# STM32F103_Debugger.net
KiCad netlist of a schematic drawn in Altium Designer
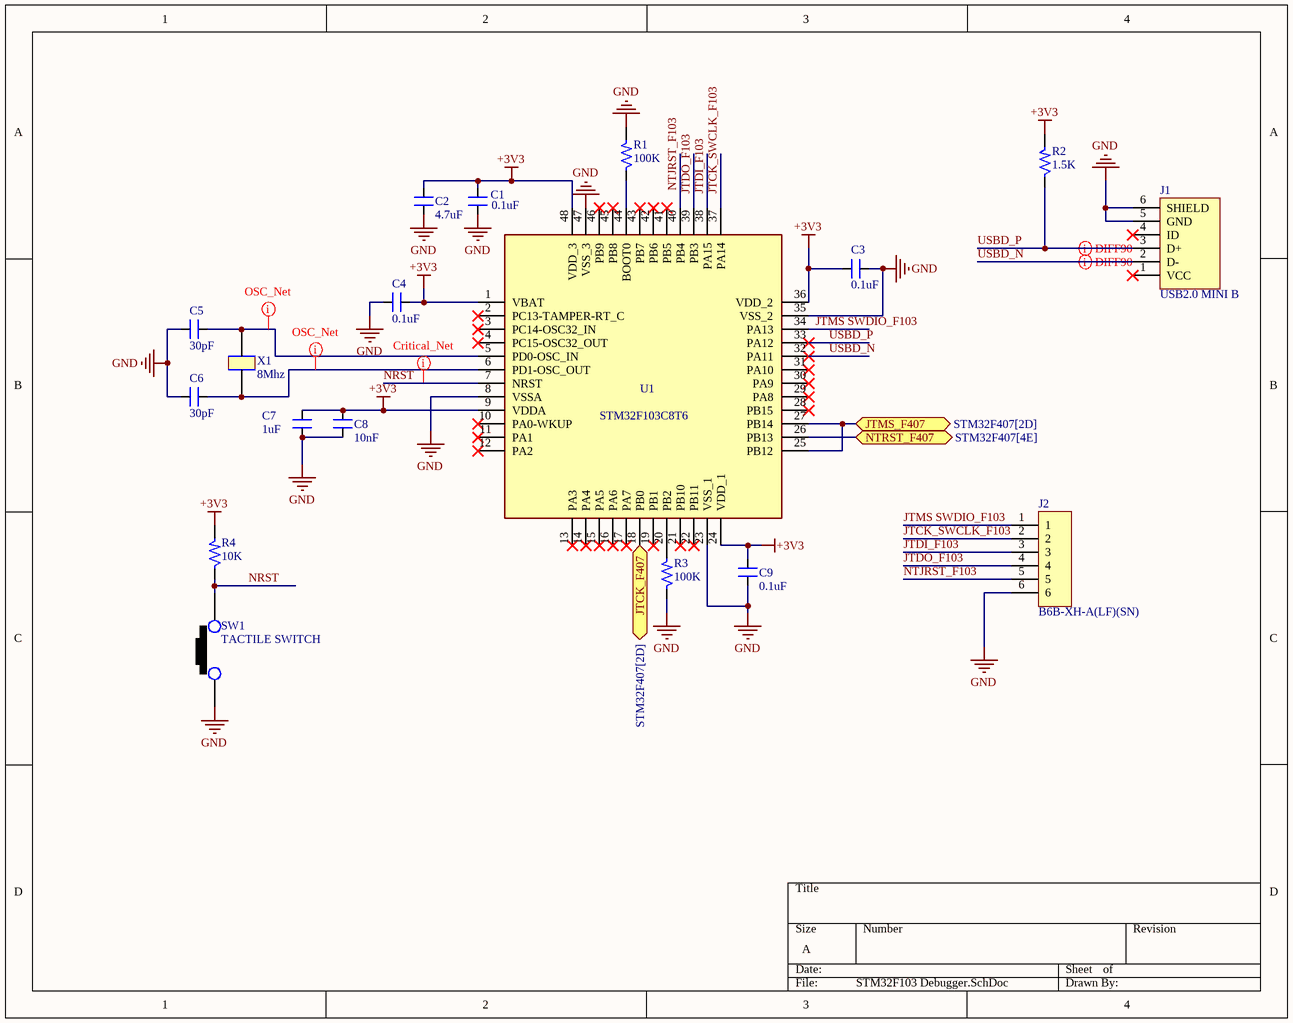
[diagram p0: STM32F103 Debugger.SchDoc]

(export (version "E")
  (design (tool "Eeschema 10.0.6"))
  (components
    (comp (ref "C1")
      (value "0.1uF")
      (footprint "CAP_0805")
      (description "0.1µF ±10% 50V Ceramic Capacitor X7R 0805 (2012 Metric)")
      (fields
        (field (name "MANUFACTURER") "Samsung")
        (field (name "MANUFACTURER PART NUMBER") "CL21B104KBCNNNC")
      )
      (libsource (lib "ESTEEMPCBLIB") (part "CAP_0.1uF-50V-10%-0805"))
    )
    (comp (ref "C2")
      (value "4.7uF")
      (footprint "CAP_0805")
      (description "4.7µF ±10% 50V Ceramic Capacitor X5R 0805 (2012 Metric)")
      (fields
        (field (name "MANUFACTURER") "Yageo")
        (field (name "MANUFACTURER PART NUMBER") "GRM21BR61H475KE51L")
      )
      (libsource (lib "ESTEEMPCBLIB") (part "CAP_4.7uF-50V-10%-0805"))
    )
    (comp (ref "C3")
      (value "0.1uF")
      (footprint "CAP_0805")
      (description "0.1µF ±10% 50V Ceramic Capacitor X7R 0805 (2012 Metric)")
      (fields
        (field (name "MANUFACTURER") "Samsung")
        (field (name "MANUFACTURER PART NUMBER") "CL21B104KBCNNNC")
      )
      (libsource (lib "ESTEEMPCBLIB") (part "CAP_0.1uF-50V-10%-0805"))
    )
    (comp (ref "C4")
      (value "0.1uF")
      (footprint "CAP_0805")
      (description "0.1µF ±10% 50V Ceramic Capacitor X7R 0805 (2012 Metric)")
      (fields
        (field (name "MANUFACTURER") "Samsung")
        (field (name "MANUFACTURER PART NUMBER") "CL21B104KBCNNNC")
      )
      (libsource (lib "ESTEEMPCBLIB") (part "CAP_0.1uF-50V-10%-0805"))
    )
    (comp (ref "C5")
      (value "30pF")
      (footprint "CAP_0805")
      (description "±10% 50V Ceramic Capacitor C0G, NP0 0805 (2012 Metric)")
      (fields
        (field (name "MANUFACTURER PART NUMBER") "C0805C300K5GAC7800")
        (field (name "MANUFACTURER") "KEMET")
      )
      (libsource (lib "ESTEEMPCBLIB") (part "CAP_30pF-50V-10%-0805"))
    )
    (comp (ref "C6")
      (value "30pF")
      (footprint "CAP_0805")
      (description "±10% 50V Ceramic Capacitor C0G, NP0 0805 (2012 Metric)")
      (fields
        (field (name "MANUFACTURER PART NUMBER") "C0805C300K5GAC7800")
        (field (name "MANUFACTURER") "KEMET")
      )
      (libsource (lib "ESTEEMPCBLIB") (part "CAP_30pF-50V-10%-0805"))
    )
    (comp (ref "C7")
      (value "1uF")
      (footprint "CAP_0805")
      (description "1µF ±5% 50V Ceramic Capacitor X7R 0805 (2012 Metric)")
      (fields
        (field (name "MANUFACTURER") "Samsung")
        (field (name "MANUFACTURER PART NUMBER") "CC0805JKX7R9BB105")
      )
      (libsource (lib "ESTEEMPCBLIB") (part "CAP_1uF-50V-5%-0805"))
    )
    (comp (ref "C8")
      (value "10nF")
      (footprint "CAP_0805")
      (description "10000pF ±10% 50V Ceramic Capacitor X7R 0805 (2012 Metric)")
      (fields
        (field (name "MANUFACTURER") "Samsung")
        (field (name "MANUFACTURER PART NUMBER") "C0805C103K5RECAUTO")
      )
      (libsource (lib "ESTEEMPCBLIB") (part "CAP_10nF-50V-10%-0805"))
    )
    (comp (ref "C9")
      (value "0.1uF")
      (footprint "CAP_0805")
      (description "0.1µF ±10% 50V Ceramic Capacitor X7R 0805 (2012 Metric)")
      (fields
        (field (name "MANUFACTURER") "Samsung")
        (field (name "MANUFACTURER PART NUMBER") "CL21B104KBCNNNC")
      )
      (libsource (lib "ESTEEMPCBLIB") (part "CAP_0.1uF-50V-10%-0805"))
    )
    (comp (ref "J1")
      (value "USB2.0 MINI B")
      (footprint "CON_690-005-299-043")
      (description "USB - mini B USB 2.0 Receptacle Connector 5 Position Surface Mount, Right Angle")
      (fields
        (field (name "MANUFACTURER") "EDAC")
        (field (name "MANUFACTURER PART NUMBER") "690-005-299-043")
      )
      (libsource (lib "ESTEEMPCBLIB") (part "CON_USB2.0-MINIB-SMD"))
    )
    (comp (ref "J2")
      (value "B6B-XH-A(LF)(SN)")
      (footprint "CON6_100_B6B-XH-A_TH_ST")
      (description "6 Pins, 1 Row 2.54mm Pitch, straight Connector, male")
      (fields (field (name "MANUFACTURER") "JST") (field (name "MATING PART NUMBER") "XHP-6"))
      (libsource (lib "ESTEEMPCBLIB") (part "CON-PLG_6X1-100-ST-TH"))
    )
    (comp (ref "R1")
      (value "100K")
      (footprint "RES_0805")
      (description "100 kOhms ±1% 0.125W, 1/8W Chip Resistor 0805 (2012 Metric) Automotive AEC-Q200 Thick Film")
      (fields (field (name "MANUFACTURER") "Walsin") (field (name "MANUFACTURER PART NUMBER") "WR08X1003FTL"))
      (libsource (lib "ESTEEMPCBLIB") (part "RES_100K-0.125W-1%-0805"))
    )
    (comp (ref "R2")
      (value "1.5K")
      (footprint "RES_0805")
      (description "1.5 kOhms ±1% 0.125W, 1/8W Chip Resistor 0805 (2012 Metric) Thick Film")
      (fields
        (field (name "MANUFACTURER") "TE Connectivity Passive Product")
        (field (name "MANUFACTURER PART NUMBER") "CRG0805F1K5")
      )
      (libsource (lib "ESTEEMPCBLIB") (part "RES_1.5K-0.125W-1%-0805"))
    )
    (comp (ref "R3")
      (value "100K")
      (footprint "RES_0805")
      (description "100 kOhms ±1% 0.125W, 1/8W Chip Resistor 0805 (2012 Metric) Automotive AEC-Q200 Thick Film")
      (fields (field (name "MANUFACTURER") "Walsin") (field (name "MANUFACTURER PART NUMBER") "WR08X1003FTL"))
      (libsource (lib "ESTEEMPCBLIB") (part "RES_100K-0.125W-1%-0805"))
    )
    (comp (ref "R4")
      (value "10K")
      (footprint "RES_0603")
      (description "10 kOhms ±1% 0.1W, 1/10W Chip Resistor 0603 (1608 Metric) Automotive AEC-Q200 Thick Film")
      (fields (field (name "MANUFACTURER") "Walsin") (field (name "MANUFACTURER PART NUMBER") "WR06X1002FTL"))
      (libsource (lib "ESTEEMPCBLIB") (part "RES_10K-0.1W-1%-0603"))
    )
    (comp (ref "SW1")
      (value "TACTILE SWITCH")
      (footprint "SW_342_SMD")
      (description "Tactile Switch SPST-NO Top Actuated Surface Mount")
      (fields
        (field (name "MANUFACTURER") "ITT C&K")
        (field (name "MANUFACTURER PART NUMBER") "RS-282G05A3-SMRT")
      )
      (libsource (lib "ESTEEMPCBLIB") (part "SW1_RS-282G05A3-SMRT-SMD"))
    )
    (comp (ref "U1")
      (value "STM32F103C8T6")
      (footprint "LQFP-48_19.6_393_58X11_SMD")
      (description "ARM® Cortex®-M3 STM32F1 Microcontroller IC 32-Bit 72MHz 64KB (64K x 8) FLASH 48-LQFP (7x7)")
      (fields (field (name "MANUFACTURER") "STMicroelectronics"))
      (libsource (lib "ESTEEMPCBLIB") (part "IC_STM32F103C8T6"))
    )
    (comp (ref "X1")
      (value "8Mhz")
      (footprint "XTAL_314_240X47_SMD")
      (description "8MHz ±30ppm Crystal 32pF 60 Ohms HC-49/US")
      (fields
        (field (name "MANUFACTURER") "Fox Electronics")
        (field (name "MANUFACTURER PART NUMBER") "ECS-80-32-5PX-TR")
      )
      (libsource (lib "ESTEEMPCBLIB") (part "XTAL_8MHZ-ECS-80-32-5PX-SMD"))
    )
  )
  (nets
    (net (code "1") (name "+3V3") (class "Default")
      (node (ref "C1") (pin "1") (pinfunction "1_1") (pintype "passive"))
      (node (ref "C2") (pin "2") (pinfunction "2_2") (pintype "passive"))
      (node (ref "C3") (pin "1") (pinfunction "1_1") (pintype "passive"))
      (node (ref "C4") (pin "2") (pinfunction "2_2") (pintype "passive"))
      (node (ref "C7") (pin "1") (pinfunction "1_1") (pintype "passive"))
      (node (ref "C8") (pin "2") (pinfunction "2_2") (pintype "passive"))
      (node (ref "C9") (pin "2") (pinfunction "2_2") (pintype "passive"))
      (node (ref "R2") (pin "2") (pinfunction "2_2") (pintype "passive"))
      (node (ref "R4") (pin "2") (pinfunction "2_2") (pintype "passive"))
      (node (ref "U1") (pin "1") (pinfunction "VBAT_1") (pintype "passive"))
      (node (ref "U1") (pin "24") (pinfunction "VDD_1_24") (pintype "passive"))
      (node (ref "U1") (pin "36") (pinfunction "VDD_2_36") (pintype "passive"))
      (node (ref "U1") (pin "48") (pinfunction "VDD_3_48") (pintype "passive"))
      (node (ref "U1") (pin "9") (pinfunction "VDDA_9") (pintype "passive"))
    )
    (net (code "2") (name "/JTCK_F407") (class "Default")
      (node (ref "U1") (pin "18") (pinfunction "PB0_18") (pintype "passive"))
    )
    (net (code "3") (name "/JTCK_SWCLK_F103") (class "Default")
      (node (ref "J2") (pin "2") (pinfunction "2_2") (pintype "passive"))
      (node (ref "U1") (pin "37") (pinfunction "PA14_37") (pintype "passive"))
    )
    (net (code "4") (name "/JTDI_F103") (class "Default")
      (node (ref "J2") (pin "3") (pinfunction "3_3") (pintype "passive"))
      (node (ref "U1") (pin "38") (pinfunction "PA15_38") (pintype "passive"))
    )
    (net (code "5") (name "/JTDO_F103") (class "Default")
      (node (ref "J2") (pin "4") (pinfunction "4_4") (pintype "passive"))
      (node (ref "U1") (pin "39") (pinfunction "PB3_39") (pintype "passive"))
    )
    (net (code "6") (name "/JTMS SWDIO_F103") (class "Default")
      (node (ref "J2") (pin "1") (pinfunction "1_1") (pintype "passive"))
      (node (ref "U1") (pin "34") (pinfunction "PA13_34") (pintype "passive"))
    )
    (net (code "7") (name "/JTMS_F407") (class "Default")
      (node (ref "U1") (pin "25") (pinfunction "PB12_25") (pintype "passive"))
      (node (ref "U1") (pin "27") (pinfunction "PB14_27") (pintype "passive"))
    )
    (net (code "8") (name "/NRST") (class "Default")
      (node (ref "R4") (pin "1") (pinfunction "1_1") (pintype "passive"))
      (node (ref "SW1") (pin "2") (pinfunction "2_2") (pintype "passive"))
      (node (ref "U1") (pin "7") (pinfunction "NRST_7") (pintype "passive"))
    )
    (net (code "9") (name "/NTJRST_F103") (class "Default")
      (node (ref "J2") (pin "5") (pinfunction "5_5") (pintype "passive"))
      (node (ref "U1") (pin "40") (pinfunction "PB4_40") (pintype "passive"))
    )
    (net (code "10") (name "/NTRST_F407") (class "Default")
      (node (ref "U1") (pin "26") (pinfunction "PB13_26") (pintype "passive"))
    )
    (net (code "11") (name "/USBD_N") (class "Default")
      (node (ref "J1") (pin "2") (pinfunction "D-_2") (pintype "passive"))
      (node (ref "U1") (pin "32") (pinfunction "PA11_32") (pintype "passive"))
    )
    (net (code "12") (name "/USBD_P") (class "Default")
      (node (ref "J1") (pin "3") (pinfunction "D+_3") (pintype "passive"))
      (node (ref "R2") (pin "1") (pinfunction "1_1") (pintype "passive"))
      (node (ref "U1") (pin "33") (pinfunction "PA12_33") (pintype "passive"))
    )
    (net (code "13") (name "GND") (class "Default")
      (node (ref "C1") (pin "2") (pinfunction "2_2") (pintype "passive"))
      (node (ref "C2") (pin "1") (pinfunction "1_1") (pintype "passive"))
      (node (ref "C3") (pin "2") (pinfunction "2_2") (pintype "passive"))
      (node (ref "C4") (pin "1") (pinfunction "1_1") (pintype "passive"))
      (node (ref "C5") (pin "1") (pinfunction "1_1") (pintype "passive"))
      (node (ref "C6") (pin "1") (pinfunction "1_1") (pintype "passive"))
      (node (ref "C7") (pin "2") (pinfunction "2_2") (pintype "passive"))
      (node (ref "C8") (pin "1") (pinfunction "1_1") (pintype "passive"))
      (node (ref "C9") (pin "1") (pinfunction "1_1") (pintype "passive"))
      (node (ref "J1") (pin "5") (pinfunction "GND_5") (pintype "passive"))
      (node (ref "J1") (pin "6") (pinfunction "SHIELD_6") (pintype "passive"))
      (node (ref "J2") (pin "6") (pinfunction "6_6") (pintype "passive"))
      (node (ref "R1") (pin "2") (pinfunction "2_2") (pintype "passive"))
      (node (ref "R3") (pin "1") (pinfunction "1_1") (pintype "passive"))
      (node (ref "SW1") (pin "1") (pinfunction "1_1") (pintype "passive"))
      (node (ref "U1") (pin "23") (pinfunction "VSS_1_23") (pintype "passive"))
      (node (ref "U1") (pin "35") (pinfunction "VSS_2_35") (pintype "passive"))
      (node (ref "U1") (pin "47") (pinfunction "VSS_3_47") (pintype "passive"))
      (node (ref "U1") (pin "8") (pinfunction "VSSA_8") (pintype "passive"))
    )
    (net (code "14") (name "Net-(U1-BOOT0)") (class "Default")
      (node (ref "R1") (pin "1") (pinfunction "1_1") (pintype "passive"))
      (node (ref "U1") (pin "44") (pinfunction "BOOT0_44") (pintype "passive"))
    )
    (net (code "15") (name "Net-(U1-PB2)") (class "Default")
      (node (ref "R3") (pin "2") (pinfunction "2_2") (pintype "passive"))
      (node (ref "U1") (pin "20") (pinfunction "PB2_20") (pintype "passive"))
    )
    (net (code "16") (name "Net-(U1-PD0-OSC_IN)") (class "Default")
      (node (ref "C5") (pin "2") (pinfunction "2_2") (pintype "passive"))
      (node (ref "U1") (pin "5") (pinfunction "PD0-OSC_IN_5") (pintype "passive"))
      (node (ref "X1") (pin "2") (pinfunction "2_2") (pintype "passive"))
    )
    (net (code "17") (name "Net-(U1-PD1-OSC_OUT)") (class "Default")
      (node (ref "C6") (pin "2") (pinfunction "2_2") (pintype "passive"))
      (node (ref "U1") (pin "6") (pinfunction "PD1-OSC_OUT_6") (pintype "passive"))
      (node (ref "X1") (pin "1") (pinfunction "1_1") (pintype "passive"))
    )
    (net (code "18") (name "unconnected-(J1-ID-Pad4)") (class "Default")
      (node (ref "J1") (pin "4") (pinfunction "ID_4") (pintype "passive+no_connect"))
    )
    (net (code "19") (name "unconnected-(J1-VCC-Pad1)") (class "Default")
      (node (ref "J1") (pin "1") (pinfunction "VCC_1") (pintype "passive+no_connect"))
    )
    (net (code "20") (name "unconnected-(U1-PA0-WKUP-Pad10)") (class "Default")
      (node (ref "U1") (pin "10") (pinfunction "PA0-WKUP_10") (pintype "passive+no_connect"))
    )
    (net (code "21") (name "unconnected-(U1-PA1-Pad11)") (class "Default")
      (node (ref "U1") (pin "11") (pinfunction "PA1_11") (pintype "passive+no_connect"))
    )
    (net (code "22") (name "unconnected-(U1-PA2-Pad12)") (class "Default")
      (node (ref "U1") (pin "12") (pinfunction "PA2_12") (pintype "passive+no_connect"))
    )
    (net (code "23") (name "unconnected-(U1-PA3-Pad13)") (class "Default")
      (node (ref "U1") (pin "13") (pinfunction "PA3_13") (pintype "passive+no_connect"))
    )
    (net (code "24") (name "unconnected-(U1-PA4-Pad14)") (class "Default")
      (node (ref "U1") (pin "14") (pinfunction "PA4_14") (pintype "passive+no_connect"))
    )
    (net (code "25") (name "unconnected-(U1-PA5-Pad15)") (class "Default")
      (node (ref "U1") (pin "15") (pinfunction "PA5_15") (pintype "passive+no_connect"))
    )
    (net (code "26") (name "unconnected-(U1-PA6-Pad16)") (class "Default")
      (node (ref "U1") (pin "16") (pinfunction "PA6_16") (pintype "passive+no_connect"))
    )
    (net (code "27") (name "unconnected-(U1-PA7-Pad17)") (class "Default")
      (node (ref "U1") (pin "17") (pinfunction "PA7_17") (pintype "passive+no_connect"))
    )
    (net (code "28") (name "unconnected-(U1-PA8-Pad29)") (class "Default")
      (node (ref "U1") (pin "29") (pinfunction "PA8_29") (pintype "passive+no_connect"))
    )
    (net (code "29") (name "unconnected-(U1-PA9-Pad30)") (class "Default")
      (node (ref "U1") (pin "30") (pinfunction "PA9_30") (pintype "passive+no_connect"))
    )
    (net (code "30") (name "unconnected-(U1-PA10-Pad31)") (class "Default")
      (node (ref "U1") (pin "31") (pinfunction "PA10_31") (pintype "passive+no_connect"))
    )
    (net (code "31") (name "unconnected-(U1-PB1-Pad19)") (class "Default")
      (node (ref "U1") (pin "19") (pinfunction "PB1_19") (pintype "passive+no_connect"))
    )
    (net (code "32") (name "unconnected-(U1-PB5-Pad41)") (class "Default")
      (node (ref "U1") (pin "41") (pinfunction "PB5_41") (pintype "passive+no_connect"))
    )
    (net (code "33") (name "unconnected-(U1-PB6-Pad42)") (class "Default")
      (node (ref "U1") (pin "42") (pinfunction "PB6_42") (pintype "passive+no_connect"))
    )
    (net (code "34") (name "unconnected-(U1-PB7-Pad43)") (class "Default")
      (node (ref "U1") (pin "43") (pinfunction "PB7_43") (pintype "passive+no_connect"))
    )
    (net (code "35") (name "unconnected-(U1-PB8-Pad45)") (class "Default")
      (node (ref "U1") (pin "45") (pinfunction "PB8_45") (pintype "passive+no_connect"))
    )
    (net (code "36") (name "unconnected-(U1-PB9-Pad46)") (class "Default")
      (node (ref "U1") (pin "46") (pinfunction "PB9_46") (pintype "passive+no_connect"))
    )
    (net (code "37") (name "unconnected-(U1-PB10-Pad21)") (class "Default")
      (node (ref "U1") (pin "21") (pinfunction "PB10_21") (pintype "passive+no_connect"))
    )
    (net (code "38") (name "unconnected-(U1-PB11-Pad22)") (class "Default")
      (node (ref "U1") (pin "22") (pinfunction "PB11_22") (pintype "passive+no_connect"))
    )
    (net (code "39") (name "unconnected-(U1-PB15-Pad28)") (class "Default")
      (node (ref "U1") (pin "28") (pinfunction "PB15_28") (pintype "passive+no_connect"))
    )
    (net (code "40") (name "unconnected-(U1-PC13-TAMPER-RT_C-Pad2)") (class "Default")
      (node (ref "U1") (pin "2") (pinfunction "PC13-TAMPER-RT_C_2") (pintype "passive+no_connect"))
    )
    (net (code "41") (name "unconnected-(U1-PC14-OSC32_IN-Pad3)") (class "Default")
      (node (ref "U1") (pin "3") (pinfunction "PC14-OSC32_IN_3") (pintype "passive+no_connect"))
    )
    (net (code "42") (name "unconnected-(U1-PC15-OSC32_OUT-Pad4)") (class "Default")
      (node (ref "U1") (pin "4") (pinfunction "PC15-OSC32_OUT_4") (pintype "passive+no_connect"))
    )
  )
)
